# Flow.net
KiCad netlist of a schematic drawn in Altium Designer
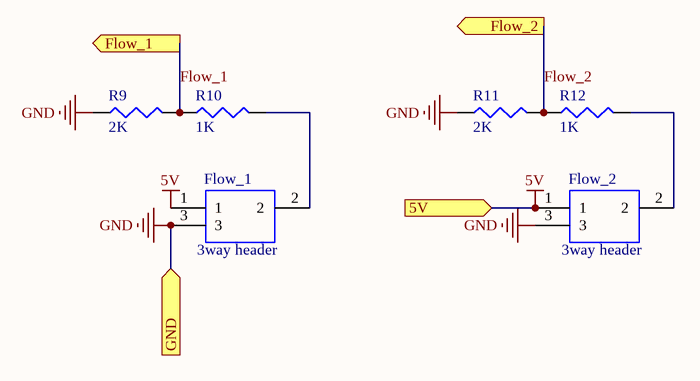
[diagram p0: Flow.SchDoc]

(export (version "E")
  (design (tool "Eeschema 10.0.6"))
  (components
    (comp (ref "Flow_1")
      (value "3way header")
      (footprint "1725669")
      (description "3 way PCB vertical mount terminal,2.54mm 3 way PCB vertical mount terminal,2.54mm")
      (fields (field (name "MANUFACTURER_PART_NUMBER") "1725669") (field (name "RS PART NUMBER") "2204276"))
      (libsource (lib "1725669") (part "1725669"))
    )
    (comp (ref "Flow_2")
      (value "3way header")
      (footprint "1725669")
      (description "3 way PCB vertical mount terminal,2.54mm 3 way PCB vertical mount terminal,2.54mm")
      (fields (field (name "MANUFACTURER_PART_NUMBER") "1725669") (field (name "RS PART NUMBER") "2204276"))
      (libsource (lib "1725669") (part "1725669"))
    )
    (comp (ref "R9")
      (value "2K")
      (footprint "J1-0603")
      (description "Resistor")
      (fields (field (name "PUBLISHER") "Altium Limited"))
      (libsource (lib "Miscellaneous Devices") (part "Res3"))
    )
    (comp (ref "R10")
      (value "1K")
      (footprint "J1-0603")
      (description "Resistor")
      (fields (field (name "PUBLISHER") "Altium Limited"))
      (libsource (lib "Miscellaneous Devices") (part "Res3"))
    )
    (comp (ref "R11")
      (value "2K")
      (footprint "J1-0603")
      (description "Resistor")
      (fields (field (name "PUBLISHER") "Altium Limited"))
      (libsource (lib "Miscellaneous Devices") (part "Res3"))
    )
    (comp (ref "R12")
      (value "1K")
      (footprint "J1-0603")
      (description "Resistor")
      (fields (field (name "PUBLISHER") "Altium Limited"))
      (libsource (lib "Miscellaneous Devices") (part "Res3"))
    )
  )
  (nets
    (net (code "1") (name "/Flow_1") (class "Default")
      (node (ref "R10") (pin "1") (pinfunction "1_1") (pintype "passive"))
      (node (ref "R9") (pin "2") (pinfunction "2_2") (pintype "passive"))
    )
    (net (code "2") (name "/Flow_2") (class "Default")
      (node (ref "R11") (pin "2") (pinfunction "2_2") (pintype "passive"))
      (node (ref "R12") (pin "1") (pinfunction "1_1") (pintype "passive"))
    )
    (net (code "3") (name "5V") (class "Default")
      (node (ref "Flow_1") (pin "1") (pinfunction "1_1") (pintype "passive"))
      (node (ref "Flow_2") (pin "1") (pinfunction "1_1") (pintype "passive"))
    )
    (net (code "4") (name "GND") (class "Default")
      (node (ref "Flow_1") (pin "3") (pinfunction "3_3") (pintype "passive"))
      (node (ref "Flow_2") (pin "3") (pinfunction "3_3") (pintype "passive"))
      (node (ref "R11") (pin "1") (pinfunction "1_1") (pintype "passive"))
      (node (ref "R9") (pin "1") (pinfunction "1_1") (pintype "passive"))
    )
    (net (code "5") (name "Net-(Flow_1-Pad2)") (class "Default")
      (node (ref "Flow_1") (pin "2") (pinfunction "2_2") (pintype "passive"))
      (node (ref "R10") (pin "2") (pinfunction "2_2") (pintype "passive"))
    )
    (net (code "6") (name "Net-(Flow_2-Pad2)") (class "Default")
      (node (ref "Flow_2") (pin "2") (pinfunction "2_2") (pintype "passive"))
      (node (ref "R12") (pin "2") (pinfunction "2_2") (pintype "passive"))
    )
  )
)
